# board-Type-C-31-M-12.net
KiCad netlist of a schematic drawn in EAGLE
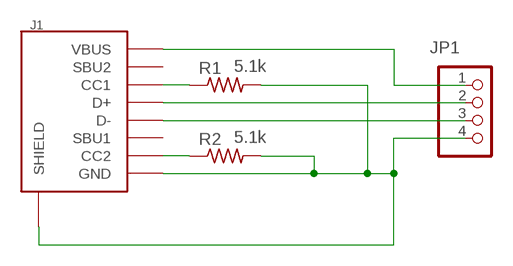
[diagram p0: schematic, sheet 1]

(export (version "E")
  (design (tool "Eeschema 10.0.6"))
  (components
    (comp (ref "J1")
      (value "USB-TYPE-C-31-M-12")
      (footprint "eagle-import:USB-TYPE-C-31-M-12")
      (libsource (lib "eagle-import") (part "USB-TYPE-C-31-M-12"))
    )
    (comp (ref "JP1")
      (value "PINHD-1X4")
      (footprint "eagle-import:1X04")
      (libsource (lib "eagle-import") (part "PINHD-1X4"))
    )
    (comp (ref "R1")
      (value "5.1k")
      (footprint "eagle-import:R0603")
      (libsource (lib "eagle-import") (part "RR0603"))
    )
    (comp (ref "R2")
      (value "5.1k")
      (footprint "eagle-import:R0603")
      (libsource (lib "eagle-import") (part "RR0603"))
    )
  )
  (nets
    (net (code "1") (name "Net-(J1-CC1)") (class "Default")
      (node (ref "J1") (pin "A5") (pinfunction "CC1_A5") (pintype "bidirectional"))
      (node (ref "R1") (pin "1") (pinfunction "1_1") (pintype "passive"))
    )
    (net (code "2") (name "Net-(J1-CC2)") (class "Default")
      (node (ref "J1") (pin "B5") (pinfunction "CC2_B5") (pintype "bidirectional"))
      (node (ref "R2") (pin "1") (pinfunction "1_1") (pintype "passive"))
    )
    (net (code "3") (name "Net-(J1-D+-PadA6)") (class "Default")
      (node (ref "J1") (pin "A6") (pinfunction "D+_A6") (pintype "bidirectional"))
      (node (ref "J1") (pin "B6") (pinfunction "D+_B6") (pintype "bidirectional"))
      (node (ref "JP1") (pin "2") (pinfunction "2_2") (pintype "passive"))
    )
    (net (code "4") (name "Net-(J1-D--PadA7)") (class "Default")
      (node (ref "J1") (pin "A7") (pinfunction "D-_A7") (pintype "bidirectional"))
      (node (ref "J1") (pin "B7") (pinfunction "D-_B7") (pintype "bidirectional"))
      (node (ref "JP1") (pin "3") (pinfunction "3_3") (pintype "passive"))
    )
    (net (code "5") (name "Net-(J1-GND-PadGND1)") (class "Default")
      (node (ref "J1") (pin "GND1") (pinfunction "GND_GND1") (pintype "bidirectional"))
      (node (ref "J1") (pin "GND2") (pinfunction "GND_GND2") (pintype "bidirectional"))
      (node (ref "J1") (pin "SHLD-B1") (pinfunction "SHIELD_SHLD-B1") (pintype "bidirectional"))
      (node (ref "J1") (pin "SHLD-B2") (pinfunction "SHIELD_SHLD-B2") (pintype "bidirectional"))
      (node (ref "J1") (pin "SHLD-B3") (pinfunction "SHIELD_SHLD-B3") (pintype "bidirectional"))
      (node (ref "J1") (pin "SHLD-B4") (pinfunction "SHIELD_SHLD-B4") (pintype "bidirectional"))
      (node (ref "J1") (pin "SHLD-T1") (pinfunction "SHIELD_SHLD-T1") (pintype "bidirectional"))
      (node (ref "J1") (pin "SHLD-T2") (pinfunction "SHIELD_SHLD-T2") (pintype "bidirectional"))
      (node (ref "J1") (pin "SHLD-T3") (pinfunction "SHIELD_SHLD-T3") (pintype "bidirectional"))
      (node (ref "J1") (pin "SHLD-T4") (pinfunction "SHIELD_SHLD-T4") (pintype "bidirectional"))
      (node (ref "JP1") (pin "4") (pinfunction "4_4") (pintype "passive"))
      (node (ref "R1") (pin "2") (pinfunction "2_2") (pintype "passive"))
      (node (ref "R2") (pin "2") (pinfunction "2_2") (pintype "passive"))
    )
    (net (code "6") (name "Net-(J1-VBUS-PadVBUS1)") (class "Default")
      (node (ref "J1") (pin "VBUS1") (pinfunction "VBUS_VBUS1") (pintype "bidirectional"))
      (node (ref "J1") (pin "VBUS2") (pinfunction "VBUS_VBUS2") (pintype "bidirectional"))
      (node (ref "JP1") (pin "1") (pinfunction "1_1") (pintype "passive"))
    )
    (net (code "7") (name "unconnected-(J1-SBU1-PadA8)") (class "Default")
      (node (ref "J1") (pin "A8") (pinfunction "SBU1_A8") (pintype "bidirectional"))
    )
    (net (code "8") (name "unconnected-(J1-SBU2-PadB8)") (class "Default")
      (node (ref "J1") (pin "B8") (pinfunction "SBU2_B8") (pintype "bidirectional"))
    )
  )
)
